# Display.net
KiCad netlist of a schematic drawn in EAGLE
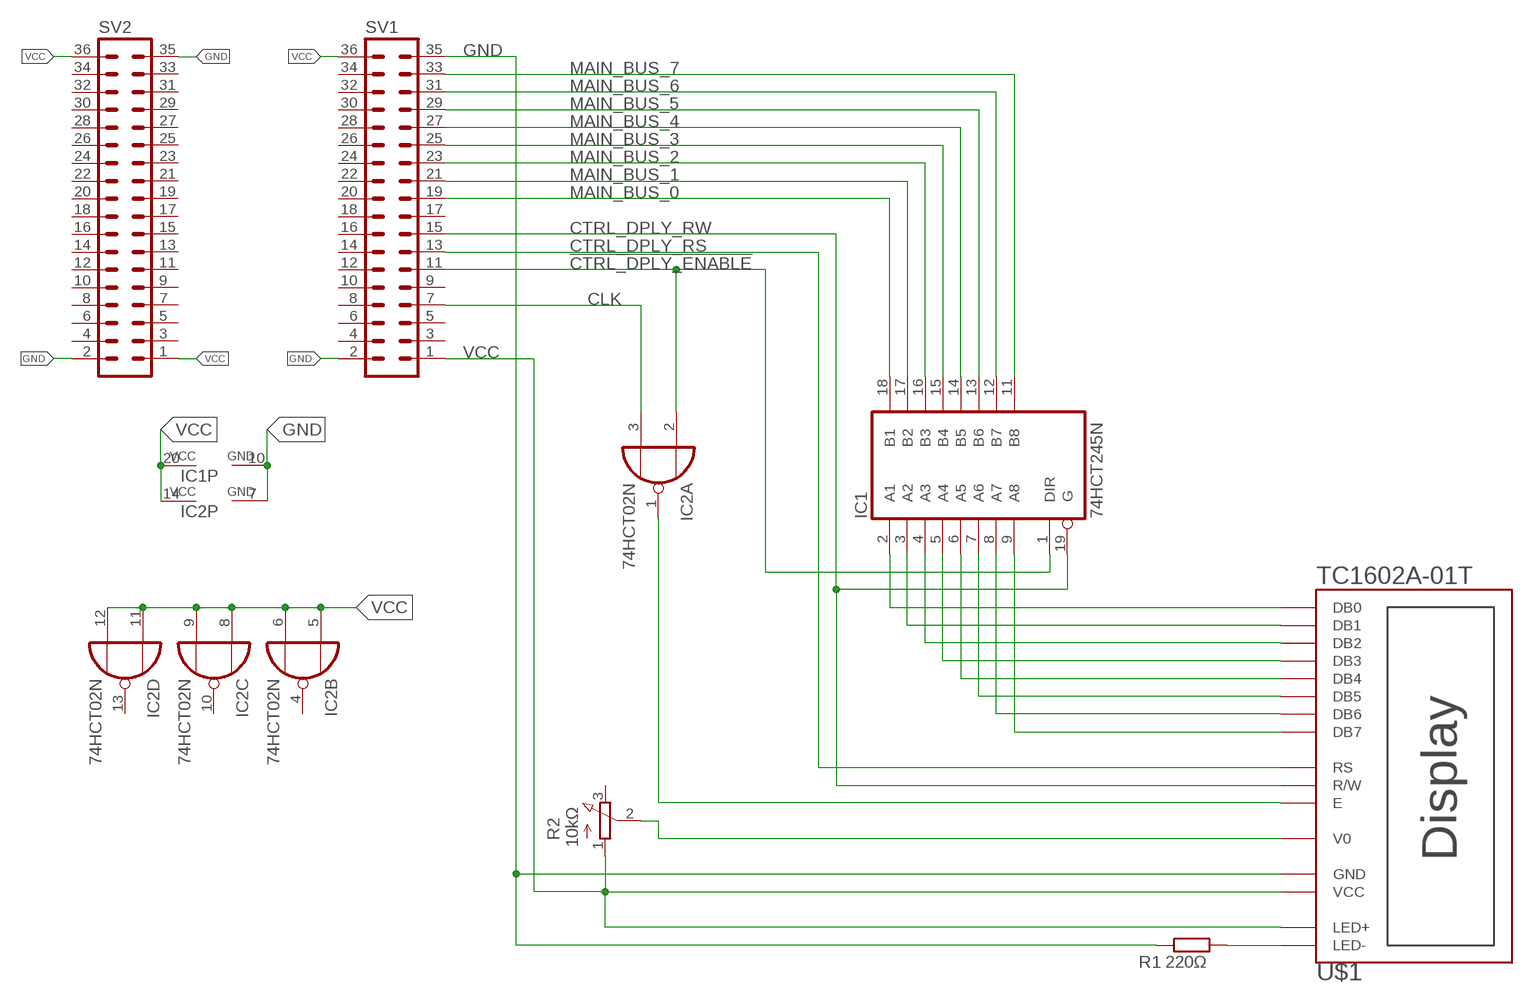
[diagram p0: schematic, sheet 1]

(export (version "E")
  (design (tool "Eeschema 10.0.6"))
  (components
    (comp (ref "IC1")
      (value "74HCT245N")
      (footprint "eagle-import:DIL20")
      (libsource (lib "eagle-import") (part "74245NHCT"))
    )
    (comp (ref "IC2")
      (value "74HCT02N")
      (footprint "eagle-import:DIL14")
      (libsource (lib "eagle-import") (part "7402NHCT"))
    )
    (comp (ref "R1")
      (value "220Ω")
      (footprint "eagle-import:0207_10")
      (libsource (lib "eagle-import") (part "R-EU_0207/10"))
    )
    (comp (ref "R2")
      (value "10kΩ")
      (footprint "eagle-import:3RP_1610N")
      (libsource (lib "eagle-import") (part "3RP/1610N"))
    )
    (comp (ref "SV1")
      (value "MA18-2")
      (footprint "eagle-import:MA18-2")
      (libsource (lib "eagle-import") (part "MA18-2"))
    )
    (comp (ref "SV2")
      (value "MA18-2")
      (footprint "eagle-import:MA18-2")
      (libsource (lib "eagle-import") (part "MA18-2"))
    )
    (comp (ref "U$1")
      (value "TC1602A-01T")
      (footprint "eagle-import:TC1602A-01T")
      (libsource (lib "eagle-import") (part "TC1602A-01T"))
    )
  )
  (nets
    (net (code "1") (name "/CLK") (class "Default")
      (node (ref "IC2") (pin "3") (pinfunction "I1_3") (pintype "input"))
      (node (ref "SV1") (pin "7") (pinfunction "7_7") (pintype "passive"))
    )
    (net (code "2") (name "/CTRL_DPLY_RS") (class "Default")
      (node (ref "SV1") (pin "13") (pinfunction "13_13") (pintype "passive"))
      (node (ref "U$1") (pin "RS") (pinfunction "RS_RS") (pintype "bidirectional"))
    )
    (net (code "3") (name "/CTRL_DPLY_RW") (class "Default")
      (node (ref "IC1") (pin "19") (pinfunction "G_19") (pintype "input"))
      (node (ref "SV1") (pin "15") (pinfunction "15_15") (pintype "passive"))
      (node (ref "U$1") (pin "R/W") (pinfunction "R/W_R/W") (pintype "bidirectional"))
    )
    (net (code "4") (name "/MAIN_BUS_0") (class "Default")
      (node (ref "IC1") (pin "18") (pinfunction "B1_18") (pintype "bidirectional"))
      (node (ref "SV1") (pin "19") (pinfunction "19_19") (pintype "passive"))
    )
    (net (code "5") (name "/MAIN_BUS_1") (class "Default")
      (node (ref "IC1") (pin "17") (pinfunction "B2_17") (pintype "bidirectional"))
      (node (ref "SV1") (pin "21") (pinfunction "21_21") (pintype "passive"))
    )
    (net (code "6") (name "/MAIN_BUS_2") (class "Default")
      (node (ref "IC1") (pin "16") (pinfunction "B3_16") (pintype "bidirectional"))
      (node (ref "SV1") (pin "23") (pinfunction "23_23") (pintype "passive"))
    )
    (net (code "7") (name "/MAIN_BUS_3") (class "Default")
      (node (ref "IC1") (pin "15") (pinfunction "B4_15") (pintype "bidirectional"))
      (node (ref "SV1") (pin "25") (pinfunction "25_25") (pintype "passive"))
    )
    (net (code "8") (name "/MAIN_BUS_4") (class "Default")
      (node (ref "IC1") (pin "14") (pinfunction "B5_14") (pintype "bidirectional"))
      (node (ref "SV1") (pin "27") (pinfunction "27_27") (pintype "passive"))
    )
    (net (code "9") (name "/MAIN_BUS_5") (class "Default")
      (node (ref "IC1") (pin "13") (pinfunction "B6_13") (pintype "bidirectional"))
      (node (ref "SV1") (pin "29") (pinfunction "29_29") (pintype "passive"))
    )
    (net (code "10") (name "/MAIN_BUS_6") (class "Default")
      (node (ref "IC1") (pin "12") (pinfunction "B7_12") (pintype "bidirectional"))
      (node (ref "SV1") (pin "31") (pinfunction "31_31") (pintype "passive"))
    )
    (net (code "11") (name "/MAIN_BUS_7") (class "Default")
      (node (ref "IC1") (pin "11") (pinfunction "B8_11") (pintype "bidirectional"))
      (node (ref "SV1") (pin "33") (pinfunction "33_33") (pintype "passive"))
    )
    (net (code "12") (name "/~{CTRL_DPLY_ENABLE}") (class "Default")
      (node (ref "IC1") (pin "1") (pinfunction "DIR_1") (pintype "input"))
      (node (ref "IC2") (pin "2") (pinfunction "I0_2") (pintype "input"))
      (node (ref "SV1") (pin "11") (pinfunction "11_11") (pintype "passive"))
    )
    (net (code "13") (name "GND") (class "Default")
      (node (ref "IC1") (pin "10") (pinfunction "GND_10") (pintype "power_in"))
      (node (ref "IC2") (pin "7") (pinfunction "GND_7") (pintype "power_in"))
      (node (ref "R1") (pin "1") (pinfunction "1_1") (pintype "passive"))
      (node (ref "SV1") (pin "2") (pinfunction "2_2") (pintype "passive"))
      (node (ref "SV1") (pin "35") (pinfunction "35_35") (pintype "passive"))
      (node (ref "SV2") (pin "2") (pinfunction "2_2") (pintype "passive"))
      (node (ref "SV2") (pin "35") (pinfunction "35_35") (pintype "passive"))
      (node (ref "U$1") (pin "GND") (pinfunction "GND_GND") (pintype "power_in"))
    )
    (net (code "14") (name "Net-(IC1A-A1)") (class "Default")
      (node (ref "IC1") (pin "2") (pinfunction "A1_2") (pintype "bidirectional"))
      (node (ref "U$1") (pin "DB0") (pinfunction "DB0_DB0") (pintype "bidirectional"))
    )
    (net (code "15") (name "Net-(IC1A-A2)") (class "Default")
      (node (ref "IC1") (pin "3") (pinfunction "A2_3") (pintype "bidirectional"))
      (node (ref "U$1") (pin "DB1") (pinfunction "DB1_DB1") (pintype "bidirectional"))
    )
    (net (code "16") (name "Net-(IC1A-A3)") (class "Default")
      (node (ref "IC1") (pin "4") (pinfunction "A3_4") (pintype "bidirectional"))
      (node (ref "U$1") (pin "DB2") (pinfunction "DB2_DB2") (pintype "bidirectional"))
    )
    (net (code "17") (name "Net-(IC1A-A4)") (class "Default")
      (node (ref "IC1") (pin "5") (pinfunction "A4_5") (pintype "bidirectional"))
      (node (ref "U$1") (pin "DB3") (pinfunction "DB3_DB3") (pintype "bidirectional"))
    )
    (net (code "18") (name "Net-(IC1A-A5)") (class "Default")
      (node (ref "IC1") (pin "6") (pinfunction "A5_6") (pintype "bidirectional"))
      (node (ref "U$1") (pin "DB4") (pinfunction "DB4_DB4") (pintype "bidirectional"))
    )
    (net (code "19") (name "Net-(IC1A-A6)") (class "Default")
      (node (ref "IC1") (pin "7") (pinfunction "A6_7") (pintype "bidirectional"))
      (node (ref "U$1") (pin "DB5") (pinfunction "DB5_DB5") (pintype "bidirectional"))
    )
    (net (code "20") (name "Net-(IC1A-A7)") (class "Default")
      (node (ref "IC1") (pin "8") (pinfunction "A7_8") (pintype "bidirectional"))
      (node (ref "U$1") (pin "DB6") (pinfunction "DB6_DB6") (pintype "bidirectional"))
    )
    (net (code "21") (name "Net-(IC1A-A8)") (class "Default")
      (node (ref "IC1") (pin "9") (pinfunction "A8_9") (pintype "bidirectional"))
      (node (ref "U$1") (pin "DB7") (pinfunction "DB7_DB7") (pintype "bidirectional"))
    )
    (net (code "22") (name "Net-(IC2A-O)") (class "Default")
      (node (ref "IC2") (pin "1") (pinfunction "O_1") (pintype "output"))
      (node (ref "U$1") (pin "E") (pinfunction "E_E") (pintype "bidirectional"))
    )
    (net (code "23") (name "Net-(R1-Pad2)") (class "Default")
      (node (ref "R1") (pin "2") (pinfunction "2_2") (pintype "passive"))
      (node (ref "U$1") (pin "LED-") (pinfunction "LED-_LED-") (pintype "bidirectional"))
    )
    (net (code "24") (name "Net-(R2-S)") (class "Default")
      (node (ref "R2") (pin "2") (pinfunction "S_2") (pintype "passive"))
      (node (ref "U$1") (pin "V0") (pinfunction "V0_V0") (pintype "bidirectional"))
    )
    (net (code "25") (name "VCC") (class "Default")
      (node (ref "IC1") (pin "20") (pinfunction "VCC_20") (pintype "power_in"))
      (node (ref "IC2") (pin "11") (pinfunction "I0_11") (pintype "input"))
      (node (ref "IC2") (pin "12") (pinfunction "I1_12") (pintype "input"))
      (node (ref "IC2") (pin "14") (pinfunction "VCC_14") (pintype "power_in"))
      (node (ref "IC2") (pin "5") (pinfunction "I0_5") (pintype "input"))
      (node (ref "IC2") (pin "6") (pinfunction "I1_6") (pintype "input"))
      (node (ref "IC2") (pin "8") (pinfunction "I0_8") (pintype "input"))
      (node (ref "IC2") (pin "9") (pinfunction "I1_9") (pintype "input"))
      (node (ref "R2") (pin "1") (pinfunction "A_1") (pintype "passive"))
      (node (ref "SV1") (pin "1") (pinfunction "1_1") (pintype "passive"))
      (node (ref "SV1") (pin "36") (pinfunction "36_36") (pintype "passive"))
      (node (ref "SV2") (pin "1") (pinfunction "1_1") (pintype "passive"))
      (node (ref "SV2") (pin "36") (pinfunction "36_36") (pintype "passive"))
      (node (ref "U$1") (pin "LED+") (pinfunction "LED+_LED+") (pintype "bidirectional"))
      (node (ref "U$1") (pin "VCC") (pinfunction "VCC_VCC") (pintype "power_in"))
    )
    (net (code "26") (name "unconnected-(IC2B-O-Pad4)") (class "Default")
      (node (ref "IC2") (pin "4") (pinfunction "O_4") (pintype "output"))
    )
    (net (code "27") (name "unconnected-(IC2C-O-Pad10)") (class "Default")
      (node (ref "IC2") (pin "10") (pinfunction "O_10") (pintype "output"))
    )
    (net (code "28") (name "unconnected-(IC2D-O-Pad13)") (class "Default")
      (node (ref "IC2") (pin "13") (pinfunction "O_13") (pintype "output"))
    )
    (net (code "29") (name "unconnected-(R2-E-Pad3)") (class "Default")
      (node (ref "R2") (pin "3") (pinfunction "E_3") (pintype "passive"))
    )
    (net (code "30") (name "unconnected-(SV1-Pad3)") (class "Default")
      (node (ref "SV1") (pin "3") (pinfunction "3_3") (pintype "passive"))
    )
    (net (code "31") (name "unconnected-(SV1-Pad4)") (class "Default")
      (node (ref "SV1") (pin "4") (pinfunction "4_4") (pintype "passive"))
    )
    (net (code "32") (name "unconnected-(SV1-Pad5)") (class "Default")
      (node (ref "SV1") (pin "5") (pinfunction "5_5") (pintype "passive"))
    )
    (net (code "33") (name "unconnected-(SV1-Pad6)") (class "Default")
      (node (ref "SV1") (pin "6") (pinfunction "6_6") (pintype "passive"))
    )
    (net (code "34") (name "unconnected-(SV1-Pad8)") (class "Default")
      (node (ref "SV1") (pin "8") (pinfunction "8_8") (pintype "passive"))
    )
    (net (code "35") (name "unconnected-(SV1-Pad9)") (class "Default")
      (node (ref "SV1") (pin "9") (pinfunction "9_9") (pintype "passive"))
    )
    (net (code "36") (name "unconnected-(SV1-Pad10)") (class "Default")
      (node (ref "SV1") (pin "10") (pinfunction "10_10") (pintype "passive"))
    )
    (net (code "37") (name "unconnected-(SV1-Pad12)") (class "Default")
      (node (ref "SV1") (pin "12") (pinfunction "12_12") (pintype "passive"))
    )
    (net (code "38") (name "unconnected-(SV1-Pad14)") (class "Default")
      (node (ref "SV1") (pin "14") (pinfunction "14_14") (pintype "passive"))
    )
    (net (code "39") (name "unconnected-(SV1-Pad16)") (class "Default")
      (node (ref "SV1") (pin "16") (pinfunction "16_16") (pintype "passive"))
    )
    (net (code "40") (name "unconnected-(SV1-Pad17)") (class "Default")
      (node (ref "SV1") (pin "17") (pinfunction "17_17") (pintype "passive"))
    )
    (net (code "41") (name "unconnected-(SV1-Pad18)") (class "Default")
      (node (ref "SV1") (pin "18") (pinfunction "18_18") (pintype "passive"))
    )
    (net (code "42") (name "unconnected-(SV1-Pad20)") (class "Default")
      (node (ref "SV1") (pin "20") (pinfunction "20_20") (pintype "passive"))
    )
    (net (code "43") (name "unconnected-(SV1-Pad22)") (class "Default")
      (node (ref "SV1") (pin "22") (pinfunction "22_22") (pintype "passive"))
    )
    (net (code "44") (name "unconnected-(SV1-Pad24)") (class "Default")
      (node (ref "SV1") (pin "24") (pinfunction "24_24") (pintype "passive"))
    )
    (net (code "45") (name "unconnected-(SV1-Pad26)") (class "Default")
      (node (ref "SV1") (pin "26") (pinfunction "26_26") (pintype "passive"))
    )
    (net (code "46") (name "unconnected-(SV1-Pad28)") (class "Default")
      (node (ref "SV1") (pin "28") (pinfunction "28_28") (pintype "passive"))
    )
    (net (code "47") (name "unconnected-(SV1-Pad30)") (class "Default")
      (node (ref "SV1") (pin "30") (pinfunction "30_30") (pintype "passive"))
    )
    (net (code "48") (name "unconnected-(SV1-Pad32)") (class "Default")
      (node (ref "SV1") (pin "32") (pinfunction "32_32") (pintype "passive"))
    )
    (net (code "49") (name "unconnected-(SV1-Pad34)") (class "Default")
      (node (ref "SV1") (pin "34") (pinfunction "34_34") (pintype "passive"))
    )
    (net (code "50") (name "unconnected-(SV2-Pad3)") (class "Default")
      (node (ref "SV2") (pin "3") (pinfunction "3_3") (pintype "passive"))
    )
    (net (code "51") (name "unconnected-(SV2-Pad4)") (class "Default")
      (node (ref "SV2") (pin "4") (pinfunction "4_4") (pintype "passive"))
    )
    (net (code "52") (name "unconnected-(SV2-Pad5)") (class "Default")
      (node (ref "SV2") (pin "5") (pinfunction "5_5") (pintype "passive"))
    )
    (net (code "53") (name "unconnected-(SV2-Pad6)") (class "Default")
      (node (ref "SV2") (pin "6") (pinfunction "6_6") (pintype "passive"))
    )
    (net (code "54") (name "unconnected-(SV2-Pad7)") (class "Default")
      (node (ref "SV2") (pin "7") (pinfunction "7_7") (pintype "passive"))
    )
    (net (code "55") (name "unconnected-(SV2-Pad8)") (class "Default")
      (node (ref "SV2") (pin "8") (pinfunction "8_8") (pintype "passive"))
    )
    (net (code "56") (name "unconnected-(SV2-Pad9)") (class "Default")
      (node (ref "SV2") (pin "9") (pinfunction "9_9") (pintype "passive"))
    )
    (net (code "57") (name "unconnected-(SV2-Pad10)") (class "Default")
      (node (ref "SV2") (pin "10") (pinfunction "10_10") (pintype "passive"))
    )
    (net (code "58") (name "unconnected-(SV2-Pad11)") (class "Default")
      (node (ref "SV2") (pin "11") (pinfunction "11_11") (pintype "passive"))
    )
    (net (code "59") (name "unconnected-(SV2-Pad12)") (class "Default")
      (node (ref "SV2") (pin "12") (pinfunction "12_12") (pintype "passive"))
    )
    (net (code "60") (name "unconnected-(SV2-Pad13)") (class "Default")
      (node (ref "SV2") (pin "13") (pinfunction "13_13") (pintype "passive"))
    )
    (net (code "61") (name "unconnected-(SV2-Pad14)") (class "Default")
      (node (ref "SV2") (pin "14") (pinfunction "14_14") (pintype "passive"))
    )
    (net (code "62") (name "unconnected-(SV2-Pad15)") (class "Default")
      (node (ref "SV2") (pin "15") (pinfunction "15_15") (pintype "passive"))
    )
    (net (code "63") (name "unconnected-(SV2-Pad16)") (class "Default")
      (node (ref "SV2") (pin "16") (pinfunction "16_16") (pintype "passive"))
    )
    (net (code "64") (name "unconnected-(SV2-Pad17)") (class "Default")
      (node (ref "SV2") (pin "17") (pinfunction "17_17") (pintype "passive"))
    )
    (net (code "65") (name "unconnected-(SV2-Pad18)") (class "Default")
      (node (ref "SV2") (pin "18") (pinfunction "18_18") (pintype "passive"))
    )
    (net (code "66") (name "unconnected-(SV2-Pad19)") (class "Default")
      (node (ref "SV2") (pin "19") (pinfunction "19_19") (pintype "passive"))
    )
    (net (code "67") (name "unconnected-(SV2-Pad20)") (class "Default")
      (node (ref "SV2") (pin "20") (pinfunction "20_20") (pintype "passive"))
    )
    (net (code "68") (name "unconnected-(SV2-Pad21)") (class "Default")
      (node (ref "SV2") (pin "21") (pinfunction "21_21") (pintype "passive"))
    )
    (net (code "69") (name "unconnected-(SV2-Pad22)") (class "Default")
      (node (ref "SV2") (pin "22") (pinfunction "22_22") (pintype "passive"))
    )
    (net (code "70") (name "unconnected-(SV2-Pad23)") (class "Default")
      (node (ref "SV2") (pin "23") (pinfunction "23_23") (pintype "passive"))
    )
    (net (code "71") (name "unconnected-(SV2-Pad24)") (class "Default")
      (node (ref "SV2") (pin "24") (pinfunction "24_24") (pintype "passive"))
    )
    (net (code "72") (name "unconnected-(SV2-Pad25)") (class "Default")
      (node (ref "SV2") (pin "25") (pinfunction "25_25") (pintype "passive"))
    )
    (net (code "73") (name "unconnected-(SV2-Pad26)") (class "Default")
      (node (ref "SV2") (pin "26") (pinfunction "26_26") (pintype "passive"))
    )
    (net (code "74") (name "unconnected-(SV2-Pad27)") (class "Default")
      (node (ref "SV2") (pin "27") (pinfunction "27_27") (pintype "passive"))
    )
    (net (code "75") (name "unconnected-(SV2-Pad28)") (class "Default")
      (node (ref "SV2") (pin "28") (pinfunction "28_28") (pintype "passive"))
    )
    (net (code "76") (name "unconnected-(SV2-Pad29)") (class "Default")
      (node (ref "SV2") (pin "29") (pinfunction "29_29") (pintype "passive"))
    )
    (net (code "77") (name "unconnected-(SV2-Pad30)") (class "Default")
      (node (ref "SV2") (pin "30") (pinfunction "30_30") (pintype "passive"))
    )
    (net (code "78") (name "unconnected-(SV2-Pad31)") (class "Default")
      (node (ref "SV2") (pin "31") (pinfunction "31_31") (pintype "passive"))
    )
    (net (code "79") (name "unconnected-(SV2-Pad32)") (class "Default")
      (node (ref "SV2") (pin "32") (pinfunction "32_32") (pintype "passive"))
    )
    (net (code "80") (name "unconnected-(SV2-Pad33)") (class "Default")
      (node (ref "SV2") (pin "33") (pinfunction "33_33") (pintype "passive"))
    )
    (net (code "81") (name "unconnected-(SV2-Pad34)") (class "Default")
      (node (ref "SV2") (pin "34") (pinfunction "34_34") (pintype "passive"))
    )
  )
)
